# snes-usb-wire.net
KiCad netlist of a schematic drawn in EAGLE
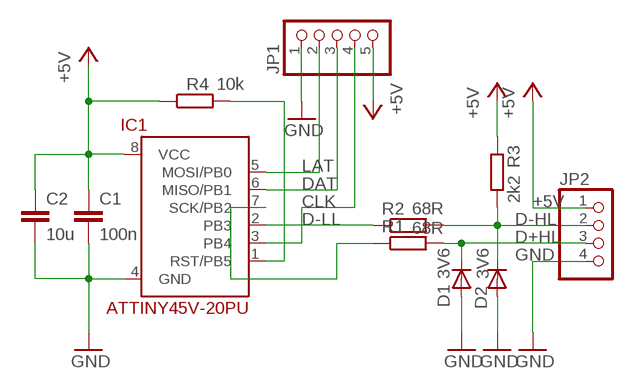
[diagram p0: schematic, sheet 1]

(export (version "E")
  (design (tool "Eeschema 10.0.6"))
  (components
    (comp (ref "C1")
      (value "100n")
      (footprint "eagle-import:C0805K")
      (libsource (lib "eagle-import") (part "C-EUC0805K"))
    )
    (comp (ref "C2")
      (value "10u")
      (footprint "eagle-import:C0805K")
      (libsource (lib "eagle-import") (part "C-EUC0805K"))
    )
    (comp (ref "D1")
      (value "3V6")
      (footprint "eagle-import:D-2.5")
      (libsource (lib "eagle-import") (part "DIODE-D-2.5"))
    )
    (comp (ref "D2")
      (value "3V6")
      (footprint "eagle-import:D-2.5")
      (libsource (lib "eagle-import") (part "DIODE-D-2.5"))
    )
    (comp (ref "IC1")
      (value "ATTINY45V-20PU")
      (footprint "eagle-import:DIL08")
      (libsource (lib "eagle-import") (part "ATTINY13V-10PU"))
    )
    (comp (ref "JP1")
      (value "PINHD-1X5")
      (footprint "eagle-import:1X05")
      (libsource (lib "eagle-import") (part "PINHD-1X5"))
    )
    (comp (ref "JP2")
      (value "PINHD-1X4")
      (footprint "eagle-import:1X04")
      (libsource (lib "eagle-import") (part "PINHD-1X4"))
    )
    (comp (ref "R1")
      (value "68R")
      (footprint "eagle-import:M0805")
      (libsource (lib "eagle-import") (part "R-EU_M0805"))
    )
    (comp (ref "R2")
      (value "68R")
      (footprint "eagle-import:M0805")
      (libsource (lib "eagle-import") (part "R-EU_M0805"))
    )
    (comp (ref "R3")
      (value "2k2")
      (footprint "eagle-import:M0805")
      (libsource (lib "eagle-import") (part "R-EU_M0805"))
    )
    (comp (ref "R4")
      (value "10k")
      (footprint "eagle-import:M0805")
      (libsource (lib "eagle-import") (part "R-EU_M0805"))
    )
  )
  (nets
    (net (code "1") (name "+5V") (class "Default")
      (node (ref "C1") (pin "1") (pinfunction "1_1") (pintype "passive"))
      (node (ref "C2") (pin "1") (pinfunction "1_1") (pintype "passive"))
      (node (ref "IC1") (pin "8") (pinfunction "VCC_8") (pintype "power_in"))
      (node (ref "JP1") (pin "5") (pinfunction "5_5") (pintype "passive"))
      (node (ref "JP2") (pin "1") (pinfunction "1_1") (pintype "passive"))
      (node (ref "R3") (pin "1") (pinfunction "1_1") (pintype "passive"))
      (node (ref "R4") (pin "1") (pinfunction "1_1") (pintype "passive"))
    )
    (net (code "2") (name "/CLK") (class "Default")
      (node (ref "IC1") (pin "3") (pinfunction "PB4_3") (pintype "bidirectional"))
      (node (ref "JP1") (pin "4") (pinfunction "4_4") (pintype "passive"))
    )
    (net (code "3") (name "/D+HL") (class "Default")
      (node (ref "D1") (pin "C") (pinfunction "C_C") (pintype "passive"))
      (node (ref "JP2") (pin "3") (pinfunction "3_3") (pintype "passive"))
      (node (ref "R1") (pin "2") (pinfunction "2_2") (pintype "passive"))
    )
    (net (code "4") (name "/D-HL") (class "Default")
      (node (ref "D2") (pin "C") (pinfunction "C_C") (pintype "passive"))
      (node (ref "JP2") (pin "2") (pinfunction "2_2") (pintype "passive"))
      (node (ref "R2") (pin "2") (pinfunction "2_2") (pintype "passive"))
      (node (ref "R3") (pin "2") (pinfunction "2_2") (pintype "passive"))
    )
    (net (code "5") (name "/D-LL") (class "Default")
      (node (ref "IC1") (pin "2") (pinfunction "PB3_2") (pintype "bidirectional"))
      (node (ref "R2") (pin "1") (pinfunction "1_1") (pintype "passive"))
    )
    (net (code "6") (name "/DAT") (class "Default")
      (node (ref "IC1") (pin "6") (pinfunction "MISO/PB1_6") (pintype "bidirectional"))
      (node (ref "JP1") (pin "3") (pinfunction "3_3") (pintype "passive"))
    )
    (net (code "7") (name "/LAT") (class "Default")
      (node (ref "IC1") (pin "5") (pinfunction "MOSI/PB0_5") (pintype "bidirectional"))
      (node (ref "JP1") (pin "2") (pinfunction "2_2") (pintype "passive"))
    )
    (net (code "8") (name "GND") (class "Default")
      (node (ref "C1") (pin "2") (pinfunction "2_2") (pintype "passive"))
      (node (ref "C2") (pin "2") (pinfunction "2_2") (pintype "passive"))
      (node (ref "D1") (pin "A") (pinfunction "A_A") (pintype "passive"))
      (node (ref "D2") (pin "A") (pinfunction "A_A") (pintype "passive"))
      (node (ref "IC1") (pin "4") (pinfunction "GND_4") (pintype "power_in"))
      (node (ref "JP1") (pin "1") (pinfunction "1_1") (pintype "passive"))
      (node (ref "JP2") (pin "4") (pinfunction "4_4") (pintype "passive"))
    )
    (net (code "9") (name "Net-(IC1-RST{slash}PB5)") (class "Default")
      (node (ref "IC1") (pin "1") (pinfunction "RST/PB5_1") (pintype "bidirectional"))
      (node (ref "R4") (pin "2") (pinfunction "2_2") (pintype "passive"))
    )
    (net (code "10") (name "Net-(IC1-SCK{slash}PB2)") (class "Default")
      (node (ref "IC1") (pin "7") (pinfunction "SCK/PB2_7") (pintype "bidirectional"))
      (node (ref "R1") (pin "1") (pinfunction "1_1") (pintype "passive"))
    )
  )
)
